# HeartRate_Sensor.net
KiCad netlist of a schematic drawn in EAGLE
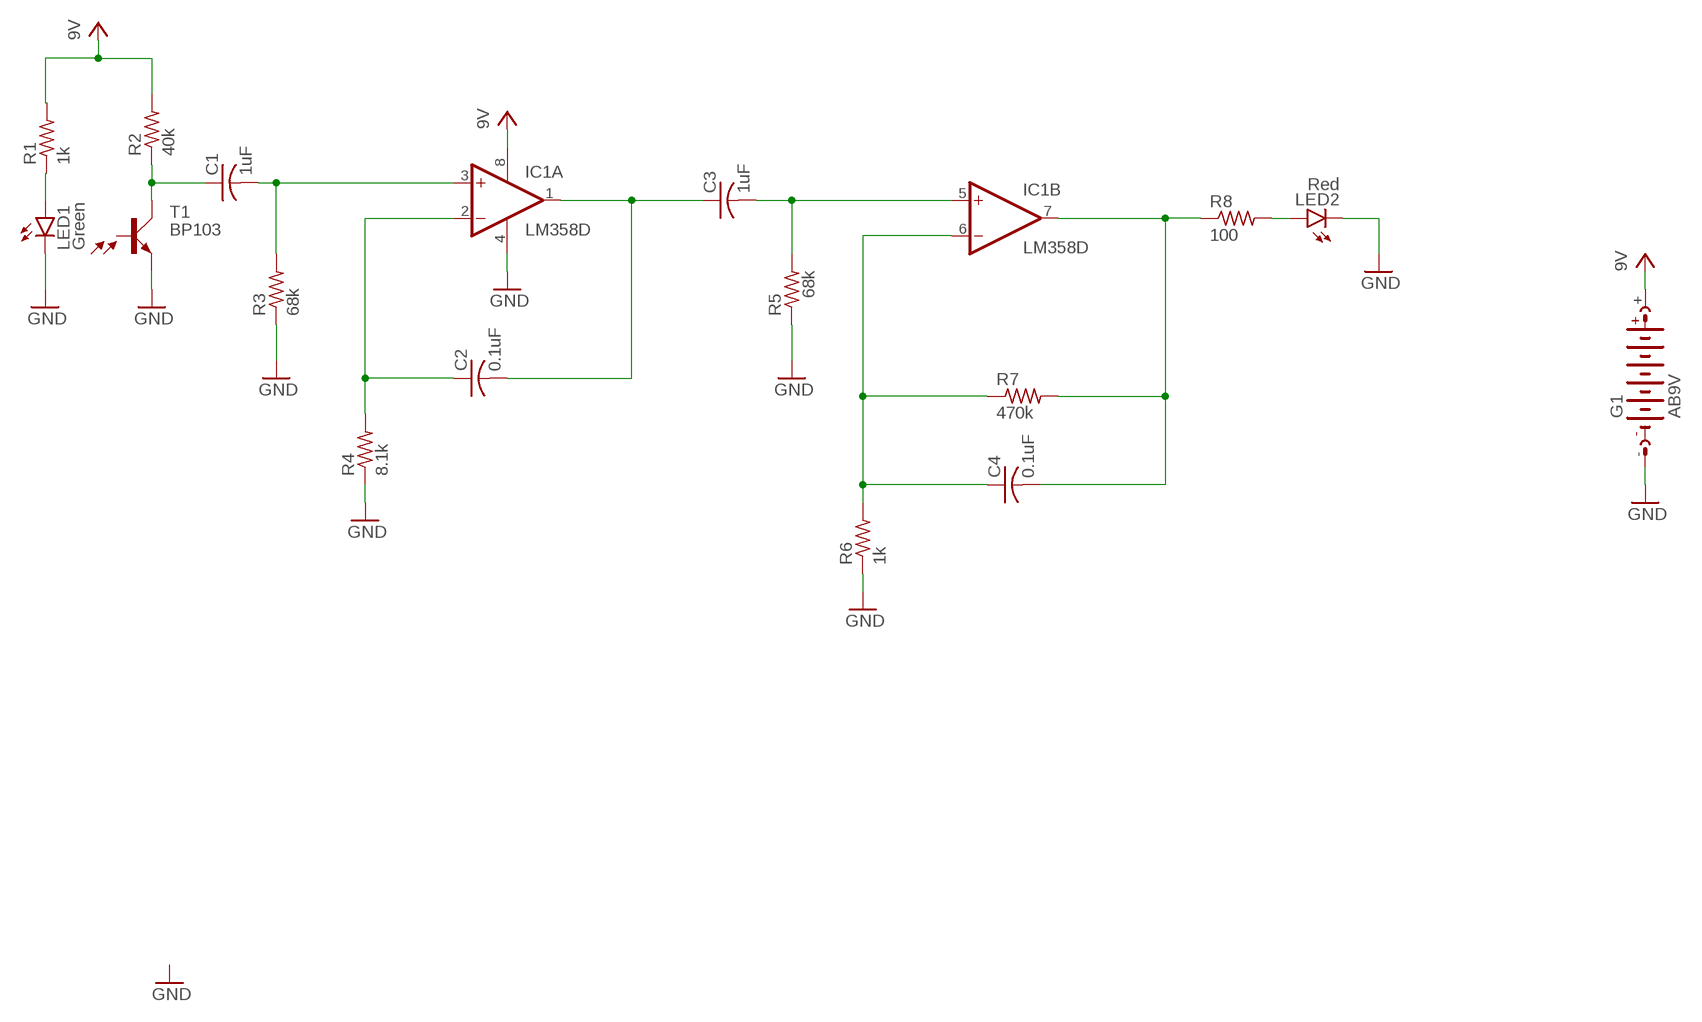
[diagram p0: schematic, sheet 1]

(export (version "E")
  (design (tool "Eeschema 10.0.6"))
  (components
    (comp (ref "C1")
      (value "1uF")
      (footprint "eagle-import:C0805")
      (libsource (lib "eagle-import") (part "C-USC0805"))
    )
    (comp (ref "C2")
      (value "0.1uF")
      (footprint "eagle-import:C0805")
      (libsource (lib "eagle-import") (part "C-USC0805"))
    )
    (comp (ref "C3")
      (value "1uF")
      (footprint "eagle-import:C0805")
      (libsource (lib "eagle-import") (part "C-USC0805"))
    )
    (comp (ref "C4")
      (value "0.1uF")
      (footprint "eagle-import:C0805")
      (libsource (lib "eagle-import") (part "C-USC0805"))
    )
    (comp (ref "G1")
      (value "AB9V")
      (footprint "eagle-import:AB9V")
      (libsource (lib "eagle-import") (part "AB9V"))
    )
    (comp (ref "IC1")
      (value "LM358D")
      (footprint "eagle-import:SO08")
      (libsource (lib "eagle-import") (part "LM358D"))
    )
    (comp (ref "LED1")
      (value "Green")
      (footprint "eagle-import:SMARTLED-TTW")
      (libsource (lib "eagle-import") (part "LED"))
    )
    (comp (ref "LED2")
      (value "Red")
      (footprint "eagle-import:SMARTLED-TTW")
      (libsource (lib "eagle-import") (part "LED"))
    )
    (comp (ref "R1")
      (value "1k")
      (footprint "eagle-import:R0805")
      (libsource (lib "eagle-import") (part "R-US_R0805"))
    )
    (comp (ref "R2")
      (value "40k")
      (footprint "eagle-import:R0805")
      (libsource (lib "eagle-import") (part "R-US_R0805"))
    )
    (comp (ref "R3")
      (value "68k")
      (footprint "eagle-import:R0805")
      (libsource (lib "eagle-import") (part "R-US_R0805"))
    )
    (comp (ref "R4")
      (value "8.1k")
      (footprint "eagle-import:R0805")
      (libsource (lib "eagle-import") (part "R-US_R0805"))
    )
    (comp (ref "R5")
      (value "68k")
      (footprint "eagle-import:R0805")
      (libsource (lib "eagle-import") (part "R-US_R0805"))
    )
    (comp (ref "R6")
      (value "1k")
      (footprint "eagle-import:R0805")
      (libsource (lib "eagle-import") (part "R-US_R0805"))
    )
    (comp (ref "R7")
      (value "470k")
      (footprint "eagle-import:R0805")
      (libsource (lib "eagle-import") (part "R-US_R0805"))
    )
    (comp (ref "R8")
      (value "100")
      (footprint "eagle-import:R0805")
      (libsource (lib "eagle-import") (part "R-US_R0805"))
    )
    (comp (ref "T1")
      (value "BP103")
      (footprint "eagle-import:BP103")
      (libsource (lib "eagle-import") (part "BP103"))
    )
  )
  (nets
    (net (code "1") (name "9V") (class "Default")
      (node (ref "G1") (pin "+") (pinfunction "+_+") (pintype "passive"))
      (node (ref "IC1") (pin "8") (pinfunction "V+_8") (pintype "power_in"))
      (node (ref "R1") (pin "2") (pinfunction "2_2") (pintype "passive"))
      (node (ref "R2") (pin "2") (pinfunction "2_2") (pintype "passive"))
    )
    (net (code "2") (name "GND") (class "Default")
      (node (ref "G1") (pin "-") (pinfunction "-_-") (pintype "passive"))
      (node (ref "IC1") (pin "4") (pinfunction "V-_4") (pintype "power_in"))
      (node (ref "LED1") (pin "C@1") (pinfunction "C_C@1") (pintype "passive"))
      (node (ref "LED2") (pin "C@1") (pinfunction "C_C@1") (pintype "passive"))
      (node (ref "R3") (pin "1") (pinfunction "1_1") (pintype "passive"))
      (node (ref "R4") (pin "1") (pinfunction "1_1") (pintype "passive"))
      (node (ref "R5") (pin "1") (pinfunction "1_1") (pintype "passive"))
      (node (ref "R6") (pin "1") (pinfunction "1_1") (pintype "passive"))
      (node (ref "T1") (pin "E") (pinfunction "E_E") (pintype "passive"))
    )
    (net (code "3") (name "Net-(C1-Pad1)") (class "Default")
      (node (ref "C1") (pin "1") (pinfunction "1_1") (pintype "passive"))
      (node (ref "R2") (pin "1") (pinfunction "1_1") (pintype "passive"))
      (node (ref "T1") (pin "C") (pinfunction "C_C") (pintype "passive"))
    )
    (net (code "4") (name "Net-(IC1A-+IN)") (class "Default")
      (node (ref "C1") (pin "2") (pinfunction "2_2") (pintype "passive"))
      (node (ref "IC1") (pin "3") (pinfunction "+IN_3") (pintype "input"))
      (node (ref "R3") (pin "2") (pinfunction "2_2") (pintype "passive"))
    )
    (net (code "5") (name "Net-(IC1A--IN)") (class "Default")
      (node (ref "C2") (pin "1") (pinfunction "1_1") (pintype "passive"))
      (node (ref "IC1") (pin "2") (pinfunction "-IN_2") (pintype "input"))
      (node (ref "R4") (pin "2") (pinfunction "2_2") (pintype "passive"))
    )
    (net (code "6") (name "Net-(IC1A-OUT)") (class "Default")
      (node (ref "C2") (pin "2") (pinfunction "2_2") (pintype "passive"))
      (node (ref "C3") (pin "1") (pinfunction "1_1") (pintype "passive"))
      (node (ref "IC1") (pin "1") (pinfunction "OUT_1") (pintype "output"))
    )
    (net (code "7") (name "Net-(IC1B-+IN)") (class "Default")
      (node (ref "C3") (pin "2") (pinfunction "2_2") (pintype "passive"))
      (node (ref "IC1") (pin "5") (pinfunction "+IN_5") (pintype "input"))
      (node (ref "R5") (pin "2") (pinfunction "2_2") (pintype "passive"))
    )
    (net (code "8") (name "Net-(IC1B--IN)") (class "Default")
      (node (ref "C4") (pin "1") (pinfunction "1_1") (pintype "passive"))
      (node (ref "IC1") (pin "6") (pinfunction "-IN_6") (pintype "input"))
      (node (ref "R6") (pin "2") (pinfunction "2_2") (pintype "passive"))
      (node (ref "R7") (pin "1") (pinfunction "1_1") (pintype "passive"))
    )
    (net (code "9") (name "Net-(IC1B-OUT)") (class "Default")
      (node (ref "C4") (pin "2") (pinfunction "2_2") (pintype "passive"))
      (node (ref "IC1") (pin "7") (pinfunction "OUT_7") (pintype "output"))
      (node (ref "R7") (pin "2") (pinfunction "2_2") (pintype "passive"))
      (node (ref "R8") (pin "1") (pinfunction "1_1") (pintype "passive"))
    )
    (net (code "10") (name "Net-(LED1-A)") (class "Default")
      (node (ref "LED1") (pin "A@1") (pinfunction "A_A@1") (pintype "passive"))
      (node (ref "R1") (pin "1") (pinfunction "1_1") (pintype "passive"))
    )
    (net (code "11") (name "Net-(LED2-A)") (class "Default")
      (node (ref "LED2") (pin "A@1") (pinfunction "A_A@1") (pintype "passive"))
      (node (ref "R8") (pin "2") (pinfunction "2_2") (pintype "passive"))
    )
    (net (code "12") (name "unconnected-(T1-PadB)") (class "Default")
      (node (ref "T1") (pin "B") (pinfunction "B_B") (pintype "passive"))
    )
  )
)
